# v1.net
KiCad netlist of a schematic drawn in EAGLE
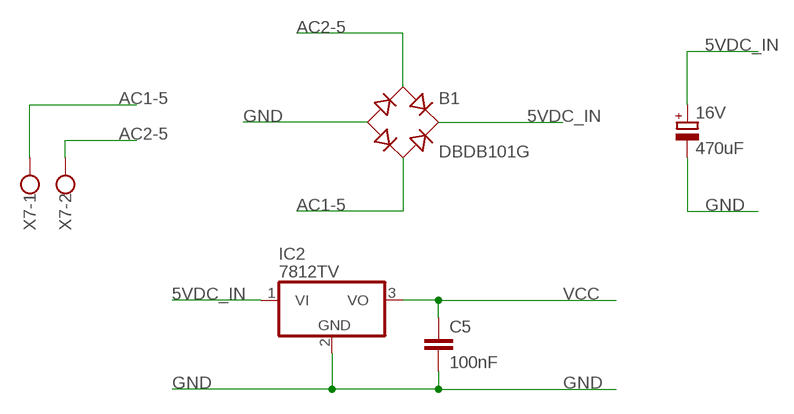
[diagram p0: schematic, sheet 1]
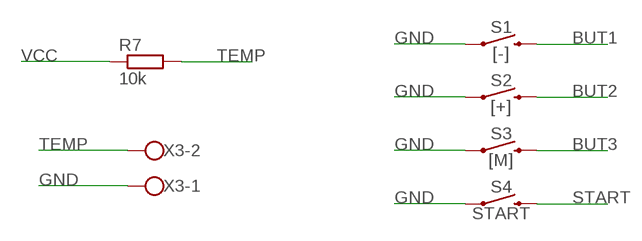
[diagram p1: schematic, sheet 2]
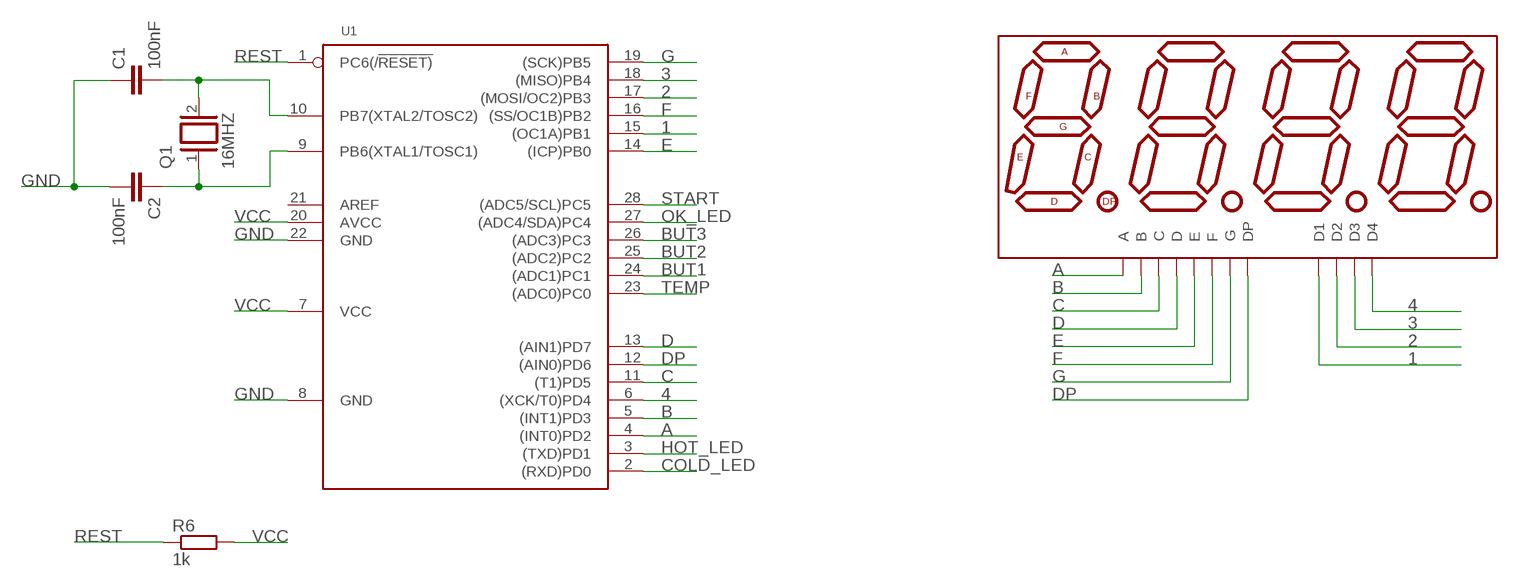
[diagram p2: schematic, sheet 3]
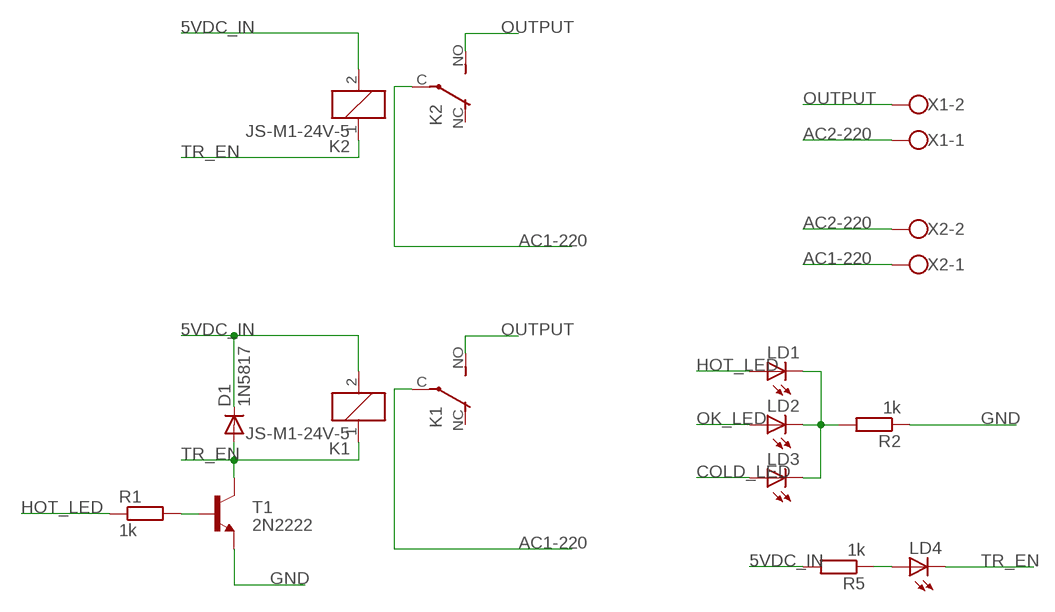
[diagram p3: schematic, sheet 4]

(export (version "E")
  (design (tool "Eeschema 10.0.6"))
  (components
    (comp (ref "R7")
      (value "10k")
      (footprint "eagle-import:0207_10")
      (libsource (lib "eagle-import") (part "R-EU_0207/10"))
    )
    (comp (ref "S1")
      (value "[-]")
      (footprint "eagle-import:TACTILE_SWITCH_PTH_6.0MM")
      (libsource (lib "eagle-import") (part "MOMENTARY-SWITCH-SPST-PTH-6.0MM"))
    )
    (comp (ref "S2")
      (value "[+]")
      (footprint "eagle-import:TACTILE_SWITCH_PTH_6.0MM")
      (libsource (lib "eagle-import") (part "MOMENTARY-SWITCH-SPST-PTH-6.0MM"))
    )
    (comp (ref "S3")
      (value "[M]")
      (footprint "eagle-import:TACTILE_SWITCH_PTH_6.0MM")
      (libsource (lib "eagle-import") (part "MOMENTARY-SWITCH-SPST-PTH-6.0MM"))
    )
    (comp (ref "S4")
      (value "START")
      (footprint "eagle-import:TACTILE_SWITCH_PTH_6.0MM")
      (libsource (lib "eagle-import") (part "MOMENTARY-SWITCH-SPST-PTH-6.0MM"))
    )
    (comp (ref "X3")
      (value "W237-102")
      (footprint "eagle-import:W237-102")
      (libsource (lib "eagle-import") (part "W237-102"))
    )
    (comp (ref "C1")
      (value "100nF")
      (footprint "eagle-import:C050-025X075")
      (libsource (lib "eagle-import") (part "C-EU050-025X075"))
    )
    (comp (ref "C2")
      (value "100nF")
      (footprint "eagle-import:C050-025X075")
      (libsource (lib "eagle-import") (part "C-EU050-025X075"))
    )
    (comp (ref "DISP2")
      (value "ATA8041AB")
      (footprint "eagle-import:7-SEGMENT-4DIGIT-20MM")
      (libsource (lib "eagle-import") (part "7-SEGMENT-4DIGIT-20MM-BLUE"))
    )
    (comp (ref "Q1")
      (value "16MHZ")
      (footprint "eagle-import:QS")
      (libsource (lib "eagle-import") (part "XTAL/S"))
    )
    (comp (ref "R6")
      (value "1k")
      (footprint "eagle-import:0207_10")
      (libsource (lib "eagle-import") (part "R-EU_0207/10"))
    )
    (comp (ref "U1")
      (value "MCU-ATMEGA328P-PU(DIP28)")
      (footprint "eagle-import:DIP28-2.54-34.7X7.62MM")
      (fields (field (name "MPN") "ATMEGA328P-PU"))
      (libsource (lib "eagle-import") (part "MCU-ATMEGA328P-PU(DIP28)"))
    )
    (comp (ref "D1")
      (value "1N5817")
      (footprint "eagle-import:DO41-10")
      (libsource (lib "eagle-import") (part "1N4004"))
    )
    (comp (ref "K1")
      (value "JS-M1-24V-5")
      (footprint "eagle-import:JS-M")
      (fields (field (name "MF") "FARNELL") (field (name "MPN") "JSM1-12V-5"))
      (libsource (lib "eagle-import") (part "JS-M1-12V-5"))
    )
    (comp (ref "K2")
      (value "JS-M1-24V-5")
      (footprint "eagle-import:JS-M")
      (fields (field (name "MF") "FARNELL") (field (name "MPN") "JSM1-12V-5"))
      (libsource (lib "eagle-import") (part "JS-M1-12V-5"))
    )
    (comp (ref "LD1")
      (value "LED5MM")
      (footprint "eagle-import:LED5MM")
      (libsource (lib "eagle-import") (part "LED5MM"))
    )
    (comp (ref "LD2")
      (value "LED5MM")
      (footprint "eagle-import:LED5MM")
      (libsource (lib "eagle-import") (part "LED5MM"))
    )
    (comp (ref "LD3")
      (value "LED5MM")
      (footprint "eagle-import:LED5MM")
      (libsource (lib "eagle-import") (part "LED5MM"))
    )
    (comp (ref "LD4")
      (value "LED5MM")
      (footprint "eagle-import:LED5MM")
      (libsource (lib "eagle-import") (part "LED5MM"))
    )
    (comp (ref "R1")
      (value "1k")
      (footprint "eagle-import:0207_10")
      (libsource (lib "eagle-import") (part "R-EU_0207/10"))
    )
    (comp (ref "R2")
      (value "1k")
      (footprint "eagle-import:0207_10")
      (libsource (lib "eagle-import") (part "R-EU_0207/10"))
    )
    (comp (ref "R5")
      (value "1k")
      (footprint "eagle-import:0207_10")
      (libsource (lib "eagle-import") (part "R-EU_0207/10"))
    )
    (comp (ref "T1")
      (value "2N2222")
      (footprint "eagle-import:TO92-EBC-OVAL")
      (libsource (lib "eagle-import") (part "2N2222"))
    )
    (comp (ref "X1")
      (value "W237-102")
      (footprint "eagle-import:W237-102")
      (libsource (lib "eagle-import") (part "W237-102"))
    )
    (comp (ref "X2")
      (value "W237-102")
      (footprint "eagle-import:W237-102")
      (libsource (lib "eagle-import") (part "W237-102"))
    )
    (comp (ref "16V")
      (value "470uF")
      (footprint "eagle-import:E3,5-8")
      (libsource (lib "eagle-import") (part "CPOL-EUE3.5-8"))
    )
    (comp (ref "B1")
      (value "DBDB101G")
      (footprint "eagle-import:DB")
      (libsource (lib "eagle-import") (part "DB?GDB101"))
    )
    (comp (ref "C5")
      (value "100nF")
      (footprint "eagle-import:C050-025X075")
      (libsource (lib "eagle-import") (part "C-EU050-025X075"))
    )
    (comp (ref "IC2")
      (value "7812TV")
      (footprint "eagle-import:TO220V")
      (libsource (lib "eagle-import") (part "78TV12"))
    )
    (comp (ref "X7")
      (value "W237-102")
      (footprint "eagle-import:W237-102")
      (libsource (lib "eagle-import") (part "W237-102"))
    )
  )
  (nets
    (net (code "1") (name "1") (class "Default")
      (node (ref "DISP2") (pin "12") (pinfunction "D1_12") (pintype "bidirectional"))
      (node (ref "U1") (pin "15") (pinfunction "(OC1A)PB1_15") (pintype "bidirectional"))
    )
    (net (code "2") (name "2") (class "Default")
      (node (ref "DISP2") (pin "9") (pinfunction "D2_9") (pintype "bidirectional"))
      (node (ref "U1") (pin "17") (pinfunction "(MOSI/OC2)PB3_17") (pintype "bidirectional"))
    )
    (net (code "3") (name "3") (class "Default")
      (node (ref "DISP2") (pin "8") (pinfunction "D3_8") (pintype "bidirectional"))
      (node (ref "U1") (pin "18") (pinfunction "(MISO)PB4_18") (pintype "bidirectional"))
    )
    (net (code "4") (name "4") (class "Default")
      (node (ref "DISP2") (pin "6") (pinfunction "D4_6") (pintype "bidirectional"))
      (node (ref "U1") (pin "6") (pinfunction "(XCK/T0)PD4_6") (pintype "bidirectional"))
    )
    (net (code "5") (name "5VDC_IN") (class "Default")
      (node (ref "16V") (pin "+") (pinfunction "+_+") (pintype "passive"))
      (node (ref "B1") (pin "+") (pinfunction "+_+") (pintype "passive"))
      (node (ref "D1") (pin "C") (pinfunction "C_C") (pintype "passive"))
      (node (ref "IC2") (pin "1") (pinfunction "VI_1") (pintype "input"))
      (node (ref "K1") (pin "2") (pinfunction "2_2") (pintype "passive"))
      (node (ref "K2") (pin "2") (pinfunction "2_2") (pintype "passive"))
      (node (ref "R5") (pin "2") (pinfunction "2_2") (pintype "passive"))
    )
    (net (code "6") (name "A") (class "Default")
      (node (ref "DISP2") (pin "11") (pinfunction "A_11") (pintype "bidirectional"))
      (node (ref "U1") (pin "4") (pinfunction "(INT0)PD2_4") (pintype "bidirectional"))
    )
    (net (code "7") (name "AC1-5") (class "Default")
      (node (ref "B1") (pin "AC2") (pinfunction "AC2_AC2") (pintype "passive"))
      (node (ref "X7") (pin "1") (pinfunction "KL_1") (pintype "passive"))
    )
    (net (code "8") (name "AC1-220") (class "Default")
      (node (ref "K1") (pin "C") (pinfunction "P_C") (pintype "passive"))
      (node (ref "K2") (pin "C") (pinfunction "P_C") (pintype "passive"))
      (node (ref "X2") (pin "1") (pinfunction "KL_1") (pintype "passive"))
    )
    (net (code "9") (name "AC2-5") (class "Default")
      (node (ref "B1") (pin "AC1") (pinfunction "AC1_AC1") (pintype "passive"))
      (node (ref "X7") (pin "2") (pinfunction "KL_2") (pintype "passive"))
    )
    (net (code "10") (name "AC2-220") (class "Default")
      (node (ref "X1") (pin "1") (pinfunction "KL_1") (pintype "passive"))
      (node (ref "X2") (pin "2") (pinfunction "KL_2") (pintype "passive"))
    )
    (net (code "11") (name "B") (class "Default")
      (node (ref "DISP2") (pin "7") (pinfunction "B_7") (pintype "bidirectional"))
      (node (ref "U1") (pin "5") (pinfunction "(INT1)PD3_5") (pintype "bidirectional"))
    )
    (net (code "12") (name "BUT1") (class "Default")
      (node (ref "S1") (pin "3") (pinfunction "2_3") (pintype "passive"))
      (node (ref "U1") (pin "24") (pinfunction "(ADC1)PC1_24") (pintype "bidirectional"))
    )
    (net (code "13") (name "BUT2") (class "Default")
      (node (ref "S2") (pin "3") (pinfunction "2_3") (pintype "passive"))
      (node (ref "U1") (pin "25") (pinfunction "(ADC2)PC2_25") (pintype "bidirectional"))
    )
    (net (code "14") (name "BUT3") (class "Default")
      (node (ref "S3") (pin "3") (pinfunction "2_3") (pintype "passive"))
      (node (ref "U1") (pin "26") (pinfunction "(ADC3)PC3_26") (pintype "bidirectional"))
    )
    (net (code "15") (name "C") (class "Default")
      (node (ref "DISP2") (pin "4") (pinfunction "C_4") (pintype "bidirectional"))
      (node (ref "U1") (pin "11") (pinfunction "(T1)PD5_11") (pintype "bidirectional"))
    )
    (net (code "16") (name "COLD_LED") (class "Default")
      (node (ref "LD3") (pin "A") (pinfunction "A_A") (pintype "passive"))
      (node (ref "U1") (pin "2") (pinfunction "(RXD)PD0_2") (pintype "bidirectional"))
    )
    (net (code "17") (name "D") (class "Default")
      (node (ref "DISP2") (pin "2") (pinfunction "D_2") (pintype "bidirectional"))
      (node (ref "U1") (pin "13") (pinfunction "(AIN1)PD7_13") (pintype "bidirectional"))
    )
    (net (code "18") (name "DP") (class "Default")
      (node (ref "DISP2") (pin "3") (pinfunction "DP_3") (pintype "bidirectional"))
      (node (ref "U1") (pin "12") (pinfunction "(AIN0)PD6_12") (pintype "bidirectional"))
    )
    (net (code "19") (name "E") (class "Default")
      (node (ref "DISP2") (pin "1") (pinfunction "E_1") (pintype "bidirectional"))
      (node (ref "U1") (pin "14") (pinfunction "(ICP)PB0_14") (pintype "bidirectional"))
    )
    (net (code "20") (name "F") (class "Default")
      (node (ref "DISP2") (pin "10") (pinfunction "F_10") (pintype "bidirectional"))
      (node (ref "U1") (pin "16") (pinfunction "(SS/OC1B)PB2_16") (pintype "bidirectional"))
    )
    (net (code "21") (name "G") (class "Default")
      (node (ref "DISP2") (pin "5") (pinfunction "G_5") (pintype "bidirectional"))
      (node (ref "U1") (pin "19") (pinfunction "(SCK)PB5_19") (pintype "bidirectional"))
    )
    (net (code "22") (name "GND") (class "Default")
      (node (ref "16V") (pin "-") (pinfunction "-_-") (pintype "passive"))
      (node (ref "B1") (pin "-") (pinfunction "-_-") (pintype "passive"))
      (node (ref "C1") (pin "1") (pinfunction "1_1") (pintype "passive"))
      (node (ref "C2") (pin "2") (pinfunction "2_2") (pintype "passive"))
      (node (ref "C5") (pin "2") (pinfunction "2_2") (pintype "passive"))
      (node (ref "IC2") (pin "2") (pinfunction "GND_2") (pintype "passive"))
      (node (ref "R2") (pin "1") (pinfunction "1_1") (pintype "passive"))
      (node (ref "S1") (pin "1") (pinfunction "1_1") (pintype "passive"))
      (node (ref "S2") (pin "1") (pinfunction "1_1") (pintype "passive"))
      (node (ref "S3") (pin "1") (pinfunction "1_1") (pintype "passive"))
      (node (ref "S4") (pin "1") (pinfunction "1_1") (pintype "passive"))
      (node (ref "T1") (pin "E") (pinfunction "E_E") (pintype "passive"))
      (node (ref "U1") (pin "22") (pinfunction "GND_22") (pintype "bidirectional"))
      (node (ref "U1") (pin "8") (pinfunction "GND_8") (pintype "bidirectional"))
      (node (ref "X3") (pin "1") (pinfunction "KL_1") (pintype "passive"))
    )
    (net (code "23") (name "HOT_LED") (class "Default")
      (node (ref "LD1") (pin "A") (pinfunction "A_A") (pintype "passive"))
      (node (ref "R1") (pin "1") (pinfunction "1_1") (pintype "passive"))
      (node (ref "U1") (pin "3") (pinfunction "(TXD)PD1_3") (pintype "bidirectional"))
    )
    (net (code "24") (name "Net-(LD1-C)") (class "Default")
      (node (ref "LD1") (pin "K") (pinfunction "C_K") (pintype "passive"))
      (node (ref "LD2") (pin "K") (pinfunction "C_K") (pintype "passive"))
      (node (ref "LD3") (pin "K") (pinfunction "C_K") (pintype "passive"))
      (node (ref "R2") (pin "2") (pinfunction "2_2") (pintype "passive"))
    )
    (net (code "25") (name "Net-(LD4-PadA)") (class "Default")
      (node (ref "LD4") (pin "A") (pinfunction "A_A") (pintype "passive"))
      (node (ref "R5") (pin "1") (pinfunction "1_1") (pintype "passive"))
    )
    (net (code "26") (name "Net-(R1-Pad2)") (class "Default")
      (node (ref "R1") (pin "2") (pinfunction "2_2") (pintype "passive"))
      (node (ref "T1") (pin "B") (pinfunction "B_B") (pintype "passive"))
    )
    (net (code "27") (name "Net-(U1-PB6(XTAL1{slash}TOSC1))") (class "Default")
      (node (ref "C2") (pin "1") (pinfunction "1_1") (pintype "passive"))
      (node (ref "Q1") (pin "1") (pinfunction "1_1") (pintype "passive"))
      (node (ref "U1") (pin "9") (pinfunction "PB6(XTAL1/TOSC1)_9") (pintype "bidirectional"))
    )
    (net (code "28") (name "Net-(U1-PB7(XTAL2{slash}TOSC2))") (class "Default")
      (node (ref "C1") (pin "2") (pinfunction "2_2") (pintype "passive"))
      (node (ref "Q1") (pin "2") (pinfunction "2_2") (pintype "passive"))
      (node (ref "U1") (pin "10") (pinfunction "PB7(XTAL2/TOSC2)_10") (pintype "bidirectional"))
    )
    (net (code "29") (name "OK_LED") (class "Default")
      (node (ref "LD2") (pin "A") (pinfunction "A_A") (pintype "passive"))
      (node (ref "U1") (pin "27") (pinfunction "(ADC4/SDA)PC4_27") (pintype "bidirectional"))
    )
    (net (code "30") (name "OUTPUT") (class "Default")
      (node (ref "K1") (pin "NO") (pinfunction "S_NO") (pintype "passive"))
      (node (ref "K2") (pin "NO") (pinfunction "S_NO") (pintype "passive"))
      (node (ref "X1") (pin "2") (pinfunction "KL_2") (pintype "passive"))
    )
    (net (code "31") (name "REST") (class "Default")
      (node (ref "R6") (pin "1") (pinfunction "1_1") (pintype "passive"))
      (node (ref "U1") (pin "1") (pinfunction "PC6(/~{RESET})_1") (pintype "bidirectional"))
    )
    (net (code "32") (name "START") (class "Default")
      (node (ref "S4") (pin "3") (pinfunction "2_3") (pintype "passive"))
      (node (ref "U1") (pin "28") (pinfunction "(ADC5/SCL)PC5_28") (pintype "bidirectional"))
    )
    (net (code "33") (name "TEMP") (class "Default")
      (node (ref "R7") (pin "2") (pinfunction "2_2") (pintype "passive"))
      (node (ref "U1") (pin "23") (pinfunction "(ADC0)PC0_23") (pintype "bidirectional"))
      (node (ref "X3") (pin "2") (pinfunction "KL_2") (pintype "passive"))
    )
    (net (code "34") (name "TR_EN") (class "Default")
      (node (ref "D1") (pin "A") (pinfunction "A_A") (pintype "passive"))
      (node (ref "K1") (pin "1") (pinfunction "1_1") (pintype "passive"))
      (node (ref "K2") (pin "1") (pinfunction "1_1") (pintype "passive"))
      (node (ref "LD4") (pin "K") (pinfunction "C_K") (pintype "passive"))
      (node (ref "T1") (pin "C") (pinfunction "C_C") (pintype "passive"))
    )
    (net (code "35") (name "VCC") (class "Default")
      (node (ref "C5") (pin "1") (pinfunction "1_1") (pintype "passive"))
      (node (ref "IC2") (pin "3") (pinfunction "VO_3") (pintype "passive"))
      (node (ref "R6") (pin "2") (pinfunction "2_2") (pintype "passive"))
      (node (ref "R7") (pin "1") (pinfunction "1_1") (pintype "passive"))
      (node (ref "U1") (pin "20") (pinfunction "AVCC_20") (pintype "bidirectional"))
      (node (ref "U1") (pin "7") (pinfunction "VCC_7") (pintype "bidirectional"))
    )
    (net (code "36") (name "unconnected-(K1B-O-PadNC)") (class "Default")
      (node (ref "K1") (pin "NC") (pinfunction "O_NC") (pintype "passive"))
    )
    (net (code "37") (name "unconnected-(K2B-O-PadNC)") (class "Default")
      (node (ref "K2") (pin "NC") (pinfunction "O_NC") (pintype "passive"))
    )
    (net (code "38") (name "unconnected-(U1-AREF-Pad21)") (class "Default")
      (node (ref "U1") (pin "21") (pinfunction "AREF_21") (pintype "bidirectional"))
    )
  )
)
